# High_Speed_User_IO.net
KiCad netlist of a schematic drawn in Altium Designer
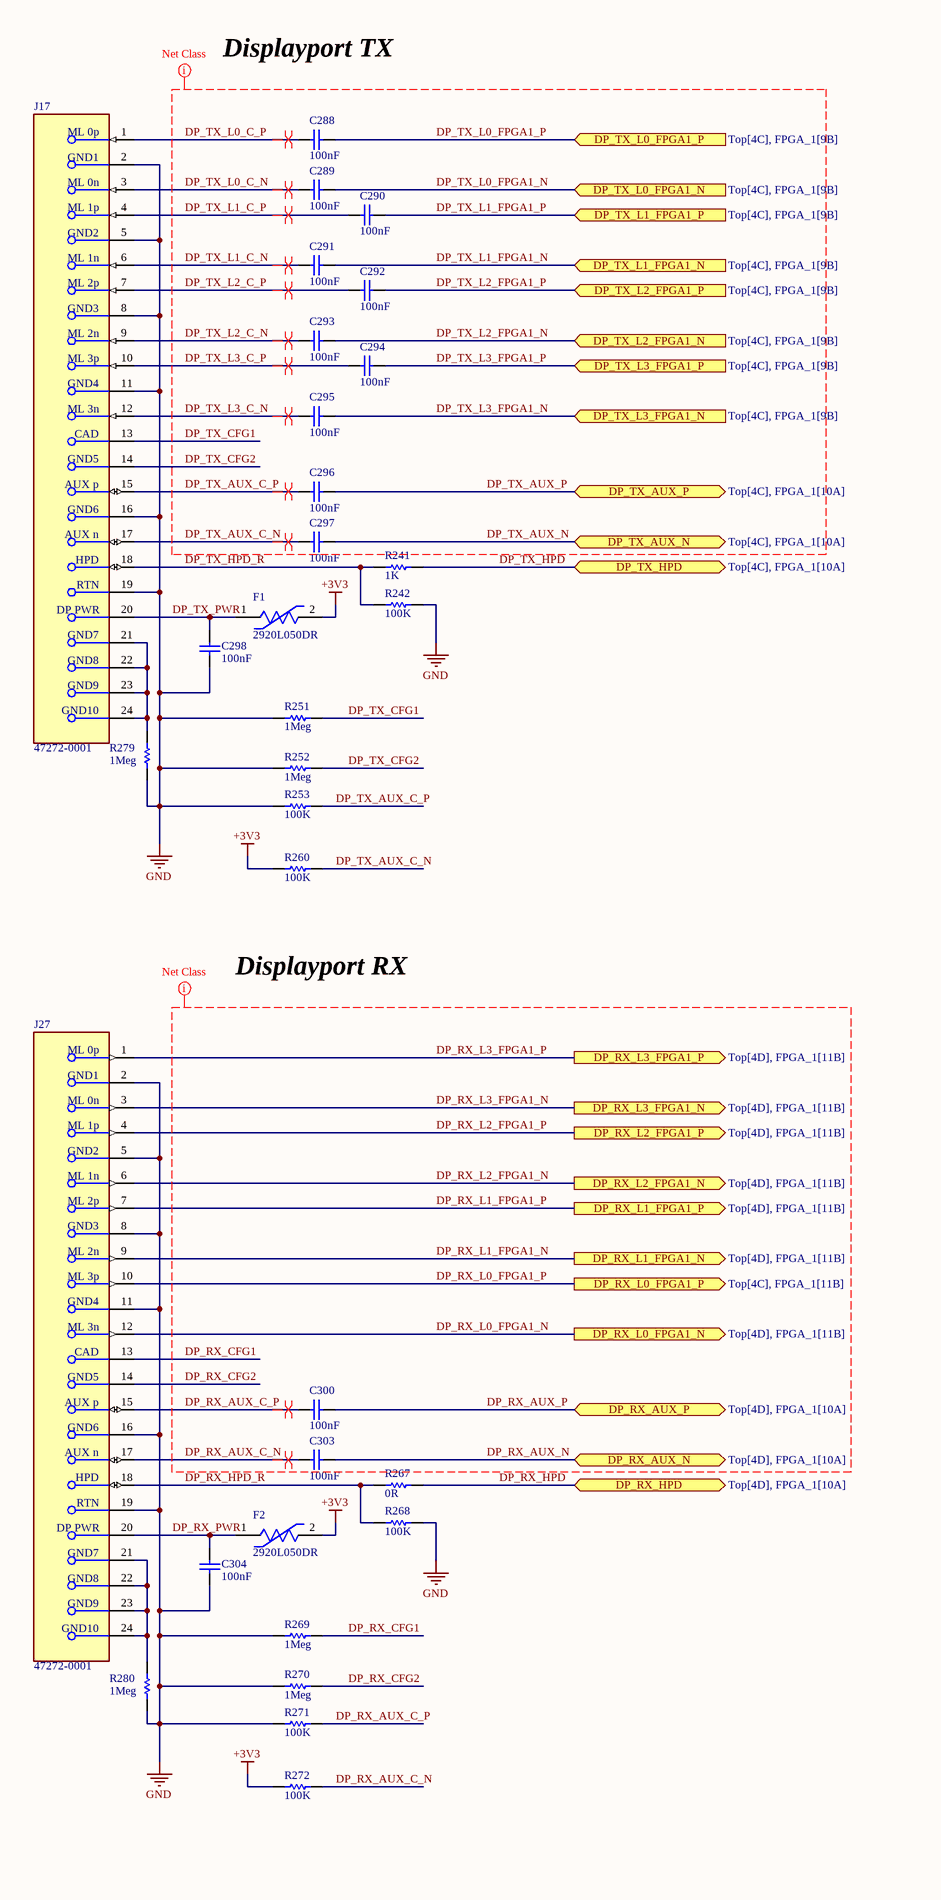
[diagram p0: High Speed User IO.SchDoc, left]
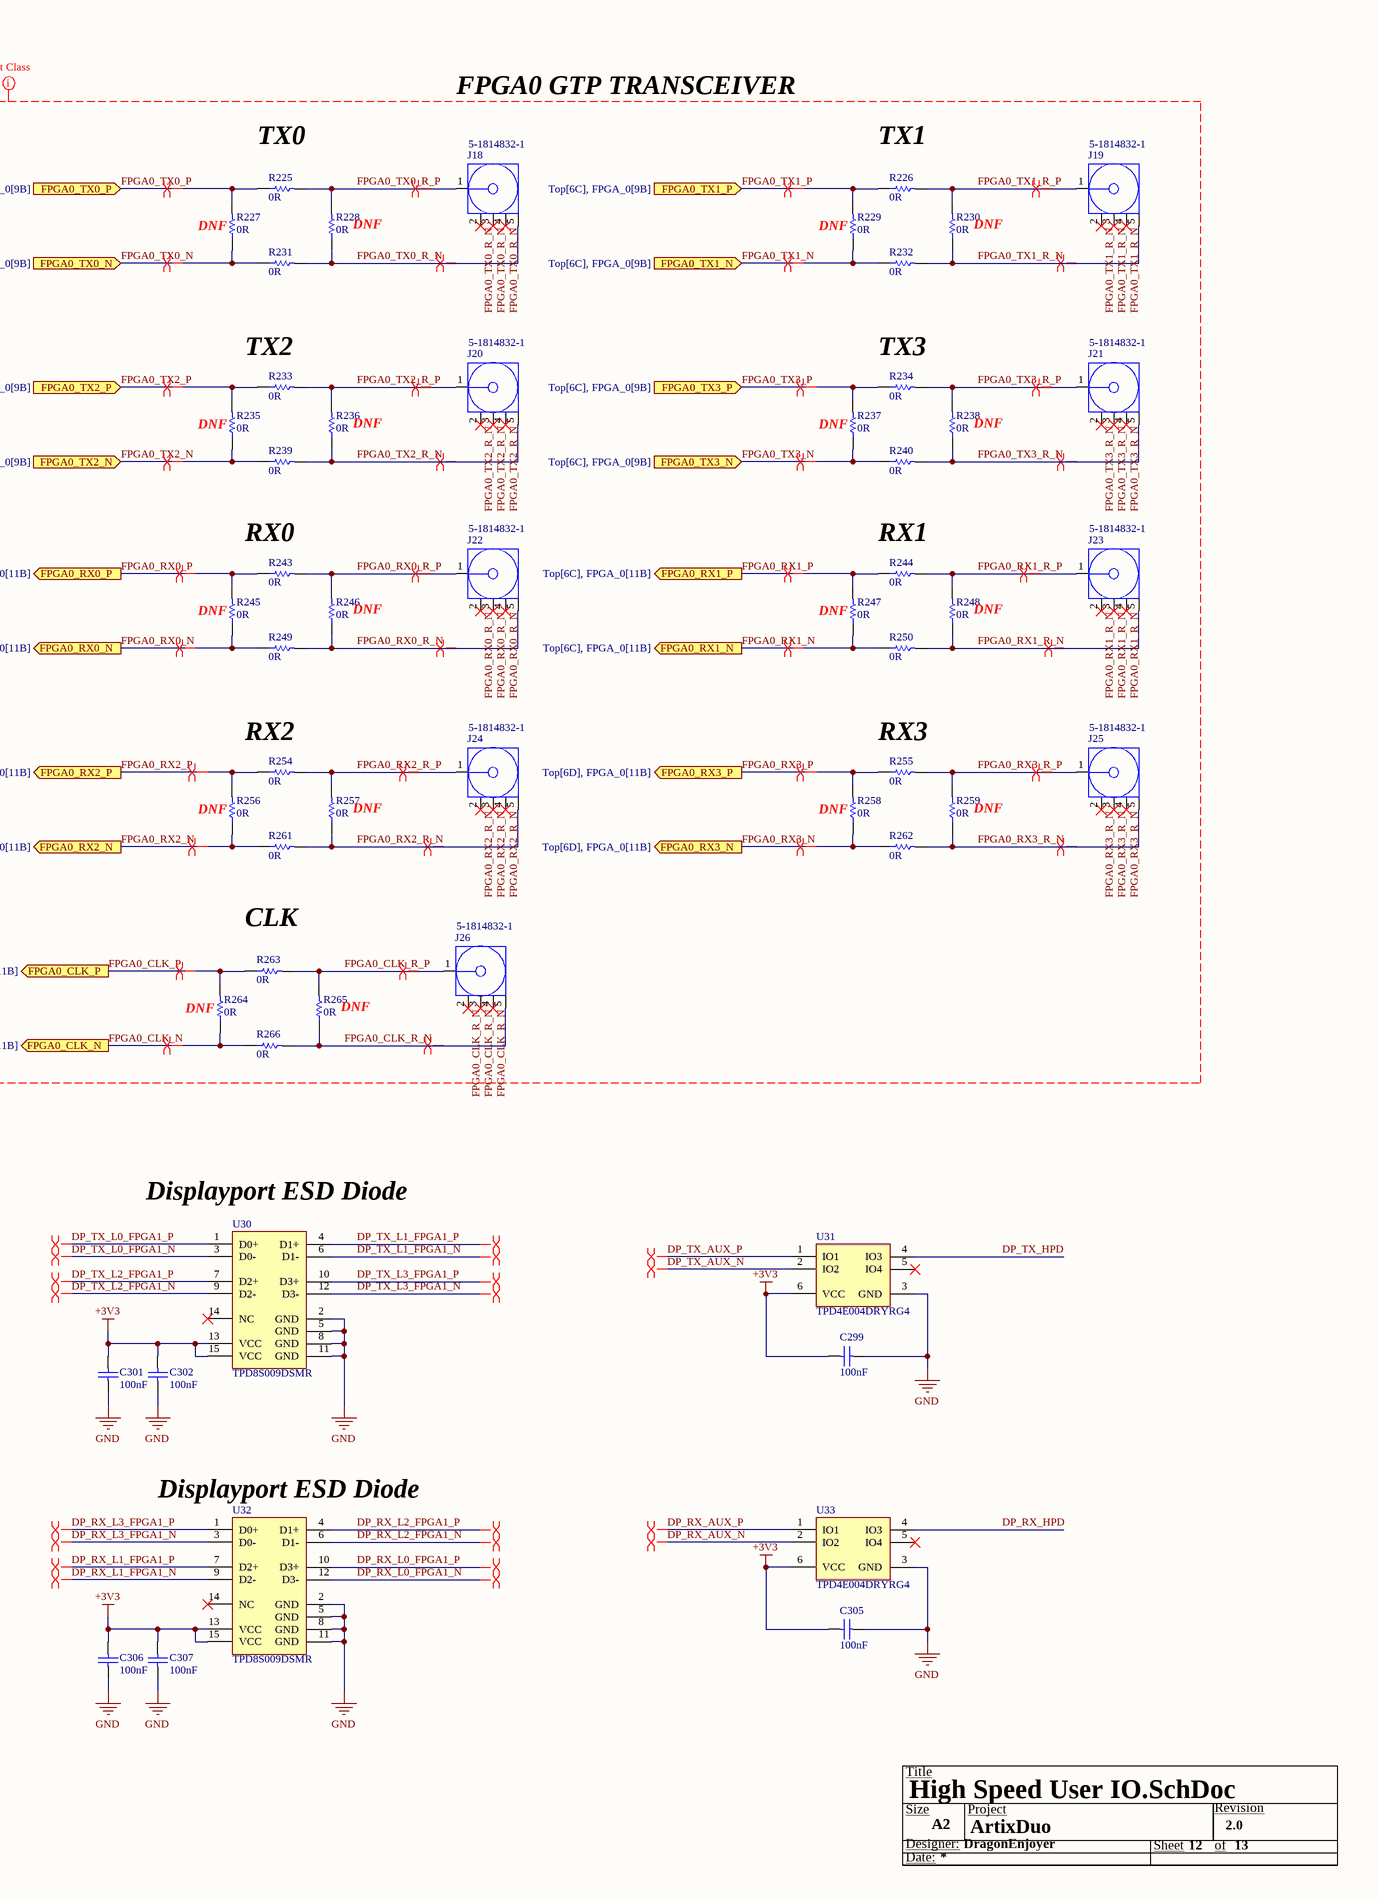
[diagram p1: High Speed User IO.SchDoc, right]

(export (version "E")
  (design (tool "Eeschema 10.0.6"))
  (components
    (comp (ref "C288")
      (value "100nF")
      (footprint "CAPC1005X05N")
      (description "Cap Ceramic 0.1uF 50V X7R 20% SMD 0402 125°C Paper T/R GRM155R71H104ME14J")
      (fields (field (name "VOLTAGE") "50V"))
      (libsource (lib "Main Workspace") (part "CAP"))
    )
    (comp (ref "C289")
      (value "100nF")
      (footprint "CAPC1005X05N")
      (description "Cap Ceramic 0.1uF 50V X7R 20% SMD 0402 125°C Paper T/R GRM155R71H104ME14J")
      (fields (field (name "VOLTAGE") "50V"))
      (libsource (lib "Main Workspace") (part "CAP"))
    )
    (comp (ref "C290")
      (value "100nF")
      (footprint "CAPC1005X05N")
      (description "Cap Ceramic 0.1uF 50V X7R 20% SMD 0402 125°C Paper T/R GRM155R71H104ME14J")
      (fields (field (name "VOLTAGE") "50V"))
      (libsource (lib "Main Workspace") (part "CAP"))
    )
    (comp (ref "C291")
      (value "100nF")
      (footprint "CAPC1005X05N")
      (description "Cap Ceramic 0.1uF 50V X7R 20% SMD 0402 125°C Paper T/R GRM155R71H104ME14J")
      (fields (field (name "VOLTAGE") "50V"))
      (libsource (lib "Main Workspace") (part "CAP"))
    )
    (comp (ref "C292")
      (value "100nF")
      (footprint "CAPC1005X05N")
      (description "Cap Ceramic 0.1uF 50V X7R 20% SMD 0402 125°C Paper T/R GRM155R71H104ME14J")
      (fields (field (name "VOLTAGE") "50V"))
      (libsource (lib "Main Workspace") (part "CAP"))
    )
    (comp (ref "C293")
      (value "100nF")
      (footprint "CAPC1005X05N")
      (description "Cap Ceramic 0.1uF 50V X7R 20% SMD 0402 125°C Paper T/R GRM155R71H104ME14J")
      (fields (field (name "VOLTAGE") "50V"))
      (libsource (lib "Main Workspace") (part "CAP"))
    )
    (comp (ref "C294")
      (value "100nF")
      (footprint "CAPC1005X05N")
      (description "Cap Ceramic 0.1uF 50V X7R 20% SMD 0402 125°C Paper T/R GRM155R71H104ME14J")
      (fields (field (name "VOLTAGE") "50V"))
      (libsource (lib "Main Workspace") (part "CAP"))
    )
    (comp (ref "C295")
      (value "100nF")
      (footprint "CAPC1005X05N")
      (description "Cap Ceramic 0.1uF 50V X7R 20% SMD 0402 125°C Paper T/R GRM155R71H104ME14J")
      (fields (field (name "VOLTAGE") "50V"))
      (libsource (lib "Main Workspace") (part "CAP"))
    )
    (comp (ref "C296")
      (value "100nF")
      (footprint "CAPC1005X05N")
      (description "Cap Ceramic 0.1uF 50V X7R 20% SMD 0402 125°C Paper T/R GRM155R71H104ME14J")
      (fields (field (name "VOLTAGE") "50V"))
      (libsource (lib "Main Workspace") (part "CAP"))
    )
    (comp (ref "C297")
      (value "100nF")
      (footprint "CAPC1005X05N")
      (description "Cap Ceramic 0.1uF 50V X7R 20% SMD 0402 125°C Paper T/R GRM155R71H104ME14J")
      (fields (field (name "VOLTAGE") "50V"))
      (libsource (lib "Main Workspace") (part "CAP"))
    )
    (comp (ref "C298")
      (value "100nF")
      (footprint "CAPC1005X05N")
      (description "Cap Ceramic 0.1uF 50V X7R 20% SMD 0402 125°C Paper T/R GRM155R71H104ME14J")
      (fields (field (name "VOLTAGE") "50V"))
      (libsource (lib "Main Workspace") (part "CAP"))
    )
    (comp (ref "C299")
      (value "100nF")
      (footprint "CAPC1005X05N")
      (description "Cap Ceramic 0.1uF 50V X7R 20% SMD 0402 125°C Paper T/R GRM155R71H104ME14J")
      (fields (field (name "VOLTAGE") "50V"))
      (libsource (lib "Main Workspace") (part "CAP"))
    )
    (comp (ref "C300")
      (value "100nF")
      (footprint "CAPC1005X05N")
      (description "Cap Ceramic 0.1uF 50V X7R 20% SMD 0402 125°C Paper T/R GRM155R71H104ME14J")
      (fields (field (name "VOLTAGE") "50V"))
      (libsource (lib "Main Workspace") (part "CAP"))
    )
    (comp (ref "C301")
      (value "100nF")
      (footprint "CAPC1005X05N")
      (description "Cap Ceramic 0.1uF 50V X7R 20% SMD 0402 125°C Paper T/R GRM155R71H104ME14J")
      (fields (field (name "VOLTAGE") "50V"))
      (libsource (lib "Main Workspace") (part "CAP"))
    )
    (comp (ref "C302")
      (value "100nF")
      (footprint "CAPC1005X05N")
      (description "Cap Ceramic 0.1uF 50V X7R 20% SMD 0402 125°C Paper T/R GRM155R71H104ME14J")
      (fields (field (name "VOLTAGE") "50V"))
      (libsource (lib "Main Workspace") (part "CAP"))
    )
    (comp (ref "C303")
      (value "100nF")
      (footprint "CAPC1005X05N")
      (description "Cap Ceramic 0.1uF 50V X7R 20% SMD 0402 125°C Paper T/R GRM155R71H104ME14J")
      (fields (field (name "VOLTAGE") "50V"))
      (libsource (lib "Main Workspace") (part "CAP"))
    )
    (comp (ref "C304")
      (value "100nF")
      (footprint "CAPC1005X05N")
      (description "Cap Ceramic 0.1uF 50V X7R 20% SMD 0402 125°C Paper T/R GRM155R71H104ME14J")
      (fields (field (name "VOLTAGE") "50V"))
      (libsource (lib "Main Workspace") (part "CAP"))
    )
    (comp (ref "C305")
      (value "100nF")
      (footprint "CAPC1005X05N")
      (description "Cap Ceramic 0.1uF 50V X7R 20% SMD 0402 125°C Paper T/R GRM155R71H104ME14J")
      (fields (field (name "VOLTAGE") "50V"))
      (libsource (lib "Main Workspace") (part "CAP"))
    )
    (comp (ref "C306")
      (value "100nF")
      (footprint "CAPC1005X05N")
      (description "Cap Ceramic 0.1uF 50V X7R 20% SMD 0402 125°C Paper T/R GRM155R71H104ME14J")
      (fields (field (name "VOLTAGE") "50V"))
      (libsource (lib "Main Workspace") (part "CAP"))
    )
    (comp (ref "C307")
      (value "100nF")
      (footprint "CAPC1005X05N")
      (description "Cap Ceramic 0.1uF 50V X7R 20% SMD 0402 125°C Paper T/R GRM155R71H104ME14J")
      (fields (field (name "VOLTAGE") "50V"))
      (libsource (lib "Main Workspace") (part "CAP"))
    )
    (comp (ref "F1")
      (value "2920L050DR")
      (footprint "FP-2920L050DR-MFG")
      (description "PTC RESET FUSE 60V 500MA 2920")
      (libsource (lib "Altium Content Vault") (part "1c6d77a0208143737455a0c7eb396be"))
    )
    (comp (ref "F2")
      (value "2920L050DR")
      (footprint "FP-2920L050DR-MFG")
      (description "PTC RESET FUSE 60V 500MA 2920")
      (libsource (lib "Altium Content Vault") (part "1c6d77a0208143737455a0c7eb396be"))
    )
    (comp (ref "J17")
      (value "47272-0001")
      (footprint "FP-47272-0001-MFG")
      (description "CONN RCPT DISPLAYPORT 20P SMD RA")
      (fields
        (field (name "MANUFACTURER") "Molex")
        (field (name "OCTOPART") "https://octopart.com/47272-0001-molex-5441289")
      )
      (libsource (lib "Altium Content Vault") (part "2afa8ceb06c8af4017661051ea5ebc1"))
    )
    (comp (ref "J18")
      (value "5-1814832-1")
      (footprint "TECO-5-1814832-1_V")
      (fields (field (name "MANUFACTURER") "TE Connectivity"))
      (libsource (lib "Altium Content Vault") (part "CN-S-4F-RF5"))
    )
    (comp (ref "J19")
      (value "5-1814832-1")
      (footprint "TECO-5-1814832-1_V")
      (fields (field (name "MANUFACTURER") "TE Connectivity"))
      (libsource (lib "Altium Content Vault") (part "CN-S-4F-RF5"))
    )
    (comp (ref "J20")
      (value "5-1814832-1")
      (footprint "TECO-5-1814832-1_V")
      (fields (field (name "MANUFACTURER") "TE Connectivity"))
      (libsource (lib "Altium Content Vault") (part "CN-S-4F-RF5"))
    )
    (comp (ref "J21")
      (value "5-1814832-1")
      (footprint "TECO-5-1814832-1_V")
      (fields (field (name "MANUFACTURER") "TE Connectivity"))
      (libsource (lib "Altium Content Vault") (part "CN-S-4F-RF5"))
    )
    (comp (ref "J22")
      (value "5-1814832-1")
      (footprint "TECO-5-1814832-1_V")
      (fields (field (name "MANUFACTURER") "TE Connectivity"))
      (libsource (lib "Altium Content Vault") (part "CN-S-4F-RF5"))
    )
    (comp (ref "J23")
      (value "5-1814832-1")
      (footprint "TECO-5-1814832-1_V")
      (fields (field (name "MANUFACTURER") "TE Connectivity"))
      (libsource (lib "Altium Content Vault") (part "CN-S-4F-RF5"))
    )
    (comp (ref "J24")
      (value "5-1814832-1")
      (footprint "TECO-5-1814832-1_V")
      (fields (field (name "MANUFACTURER") "TE Connectivity"))
      (libsource (lib "Altium Content Vault") (part "CN-S-4F-RF5"))
    )
    (comp (ref "J25")
      (value "5-1814832-1")
      (footprint "TECO-5-1814832-1_V")
      (fields (field (name "MANUFACTURER") "TE Connectivity"))
      (libsource (lib "Altium Content Vault") (part "CN-S-4F-RF5"))
    )
    (comp (ref "J26")
      (value "5-1814832-1")
      (footprint "TECO-5-1814832-1_V")
      (fields (field (name "MANUFACTURER") "TE Connectivity"))
      (libsource (lib "Altium Content Vault") (part "CN-S-4F-RF5"))
    )
    (comp (ref "J27")
      (value "47272-0001")
      (footprint "FP-47272-0001-MFG")
      (description "CONN RCPT DISPLAYPORT 20P SMD RA")
      (fields
        (field (name "MANUFACTURER") "Molex")
        (field (name "OCTOPART") "https://octopart.com/47272-0001-molex-5441289")
      )
      (libsource (lib "Altium Content Vault") (part "2afa8ceb06c8af4017661051ea5ebc1"))
    )
    (comp (ref "R225")
      (value "0R")
      (footprint "RESC1005X40X25NL05T10")
      (description "CRCW04020000Z0EDHP")
      (fields (field (name "MANUFACTURER") "Vishay Dale"))
      (libsource (lib "Altium Content Vault") (part "RES"))
    )
    (comp (ref "R226")
      (value "0R")
      (footprint "RESC1005X40X25NL05T10")
      (description "CRCW04020000Z0EDHP")
      (fields (field (name "MANUFACTURER") "Vishay Dale"))
      (libsource (lib "Altium Content Vault") (part "RES"))
    )
    (comp (ref "R227")
      (value "0R")
      (footprint "RESC1005X40X25NL05T10")
      (description "CRCW04020000Z0EDHP")
      (fields (field (name "MANUFACTURER") "Vishay Dale"))
      (libsource (lib "Altium Content Vault") (part "RES"))
    )
    (comp (ref "R228")
      (value "0R")
      (footprint "RESC1005X40X25NL05T10")
      (description "CRCW04020000Z0EDHP")
      (fields (field (name "MANUFACTURER") "Vishay Dale"))
      (libsource (lib "Altium Content Vault") (part "RES"))
    )
    (comp (ref "R229")
      (value "0R")
      (footprint "RESC1005X40X25NL05T10")
      (description "CRCW04020000Z0EDHP")
      (fields (field (name "MANUFACTURER") "Vishay Dale"))
      (libsource (lib "Altium Content Vault") (part "RES"))
    )
    (comp (ref "R230")
      (value "0R")
      (footprint "RESC1005X40X25NL05T10")
      (description "CRCW04020000Z0EDHP")
      (fields (field (name "MANUFACTURER") "Vishay Dale"))
      (libsource (lib "Altium Content Vault") (part "RES"))
    )
    (comp (ref "R231")
      (value "0R")
      (footprint "RESC1005X40X25NL05T10")
      (description "CRCW04020000Z0EDHP")
      (fields (field (name "MANUFACTURER") "Vishay Dale"))
      (libsource (lib "Altium Content Vault") (part "RES"))
    )
    (comp (ref "R232")
      (value "0R")
      (footprint "RESC1005X40X25NL05T10")
      (description "CRCW04020000Z0EDHP")
      (fields (field (name "MANUFACTURER") "Vishay Dale"))
      (libsource (lib "Altium Content Vault") (part "RES"))
    )
    (comp (ref "R233")
      (value "0R")
      (footprint "RESC1005X40X25NL05T10")
      (description "CRCW04020000Z0EDHP")
      (fields (field (name "MANUFACTURER") "Vishay Dale"))
      (libsource (lib "Altium Content Vault") (part "RES"))
    )
    (comp (ref "R234")
      (value "0R")
      (footprint "RESC1005X40X25NL05T10")
      (description "CRCW04020000Z0EDHP")
      (fields (field (name "MANUFACTURER") "Vishay Dale"))
      (libsource (lib "Altium Content Vault") (part "RES"))
    )
    (comp (ref "R235")
      (value "0R")
      (footprint "RESC1005X40X25NL05T10")
      (description "CRCW04020000Z0EDHP")
      (fields (field (name "MANUFACTURER") "Vishay Dale"))
      (libsource (lib "Altium Content Vault") (part "RES"))
    )
    (comp (ref "R236")
      (value "0R")
      (footprint "RESC1005X40X25NL05T10")
      (description "CRCW04020000Z0EDHP")
      (fields (field (name "MANUFACTURER") "Vishay Dale"))
      (libsource (lib "Altium Content Vault") (part "RES"))
    )
    (comp (ref "R237")
      (value "0R")
      (footprint "RESC1005X40X25NL05T10")
      (description "CRCW04020000Z0EDHP")
      (fields (field (name "MANUFACTURER") "Vishay Dale"))
      (libsource (lib "Altium Content Vault") (part "RES"))
    )
    (comp (ref "R238")
      (value "0R")
      (footprint "RESC1005X40X25NL05T10")
      (description "CRCW04020000Z0EDHP")
      (fields (field (name "MANUFACTURER") "Vishay Dale"))
      (libsource (lib "Altium Content Vault") (part "RES"))
    )
    (comp (ref "R239")
      (value "0R")
      (footprint "RESC1005X40X25NL05T10")
      (description "CRCW04020000Z0EDHP")
      (fields (field (name "MANUFACTURER") "Vishay Dale"))
      (libsource (lib "Altium Content Vault") (part "RES"))
    )
    (comp (ref "R240")
      (value "0R")
      (footprint "RESC1005X40X25NL05T10")
      (description "CRCW04020000Z0EDHP")
      (fields (field (name "MANUFACTURER") "Vishay Dale"))
      (libsource (lib "Altium Content Vault") (part "RES"))
    )
    (comp (ref "R241")
      (value "1K")
      (footprint "RESC1005X40X25NL05T10")
      (description "CRCW04021K00FKEDHP")
      (fields (field (name "MANUFACTURER") "Vishay Dale"))
      (libsource (lib "Altium Content Vault") (part "RES"))
    )
    (comp (ref "R242")
      (value "100K")
      (footprint "RESC1005X40X25NL05T05")
      (description "CRCW0402100KJNED")
      (fields (field (name "MANUFACTURER") "Vishay Dale"))
      (libsource (lib "Altium Content Vault") (part "RES"))
    )
    (comp (ref "R243")
      (value "0R")
      (footprint "RESC1005X40X25NL05T10")
      (description "CRCW04020000Z0EDHP")
      (fields (field (name "MANUFACTURER") "Vishay Dale"))
      (libsource (lib "Altium Content Vault") (part "RES"))
    )
    (comp (ref "R244")
      (value "0R")
      (footprint "RESC1005X40X25NL05T10")
      (description "CRCW04020000Z0EDHP")
      (fields (field (name "MANUFACTURER") "Vishay Dale"))
      (libsource (lib "Altium Content Vault") (part "RES"))
    )
    (comp (ref "R245")
      (value "0R")
      (footprint "RESC1005X40X25NL05T10")
      (description "CRCW04020000Z0EDHP")
      (fields (field (name "MANUFACTURER") "Vishay Dale"))
      (libsource (lib "Altium Content Vault") (part "RES"))
    )
    (comp (ref "R246")
      (value "0R")
      (footprint "RESC1005X40X25NL05T10")
      (description "CRCW04020000Z0EDHP")
      (fields (field (name "MANUFACTURER") "Vishay Dale"))
      (libsource (lib "Altium Content Vault") (part "RES"))
    )
    (comp (ref "R247")
      (value "0R")
      (footprint "RESC1005X40X25NL05T10")
      (description "CRCW04020000Z0EDHP")
      (fields (field (name "MANUFACTURER") "Vishay Dale"))
      (libsource (lib "Altium Content Vault") (part "RES"))
    )
    (comp (ref "R248")
      (value "0R")
      (footprint "RESC1005X40X25NL05T10")
      (description "CRCW04020000Z0EDHP")
      (fields (field (name "MANUFACTURER") "Vishay Dale"))
      (libsource (lib "Altium Content Vault") (part "RES"))
    )
    (comp (ref "R249")
      (value "0R")
      (footprint "RESC1005X40X25NL05T10")
      (description "CRCW04020000Z0EDHP")
      (fields (field (name "MANUFACTURER") "Vishay Dale"))
      (libsource (lib "Altium Content Vault") (part "RES"))
    )
    (comp (ref "R250")
      (value "0R")
      (footprint "RESC1005X40X25NL05T10")
      (description "CRCW04020000Z0EDHP")
      (fields (field (name "MANUFACTURER") "Vishay Dale"))
      (libsource (lib "Altium Content Vault") (part "RES"))
    )
    (comp (ref "R251")
      (value "1Meg")
      (footprint "RESC1005X40X25NL05T05")
      (description "ERJ-2GEJ105X")
      (fields (field (name "MANUFACTURER") "Panasonic"))
      (libsource (lib "Altium Content Vault") (part "RES"))
    )
    (comp (ref "R252")
      (value "1Meg")
      (footprint "RESC1005X40X25NL05T05")
      (description "ERJ-2GEJ105X")
      (fields (field (name "MANUFACTURER") "Panasonic"))
      (libsource (lib "Altium Content Vault") (part "RES"))
    )
    (comp (ref "R253")
      (value "100K")
      (footprint "RESC1005X40X25NL05T05")
      (description "CRCW0402100KJNED")
      (fields (field (name "MANUFACTURER") "Vishay Dale"))
      (libsource (lib "Altium Content Vault") (part "RES"))
    )
    (comp (ref "R254")
      (value "0R")
      (footprint "RESC1005X40X25NL05T10")
      (description "CRCW04020000Z0EDHP")
      (fields (field (name "MANUFACTURER") "Vishay Dale"))
      (libsource (lib "Altium Content Vault") (part "RES"))
    )
    (comp (ref "R255")
      (value "0R")
      (footprint "RESC1005X40X25NL05T10")
      (description "CRCW04020000Z0EDHP")
      (fields (field (name "MANUFACTURER") "Vishay Dale"))
      (libsource (lib "Altium Content Vault") (part "RES"))
    )
    (comp (ref "R256")
      (value "0R")
      (footprint "RESC1005X40X25NL05T10")
      (description "CRCW04020000Z0EDHP")
      (fields (field (name "MANUFACTURER") "Vishay Dale"))
      (libsource (lib "Altium Content Vault") (part "RES"))
    )
    (comp (ref "R257")
      (value "0R")
      (footprint "RESC1005X40X25NL05T10")
      (description "CRCW04020000Z0EDHP")
      (fields (field (name "MANUFACTURER") "Vishay Dale"))
      (libsource (lib "Altium Content Vault") (part "RES"))
    )
    (comp (ref "R258")
      (value "0R")
      (footprint "RESC1005X40X25NL05T10")
      (description "CRCW04020000Z0EDHP")
      (fields (field (name "MANUFACTURER") "Vishay Dale"))
      (libsource (lib "Altium Content Vault") (part "RES"))
    )
    (comp (ref "R259")
      (value "0R")
      (footprint "RESC1005X40X25NL05T10")
      (description "CRCW04020000Z0EDHP")
      (fields (field (name "MANUFACTURER") "Vishay Dale"))
      (libsource (lib "Altium Content Vault") (part "RES"))
    )
    (comp (ref "R260")
      (value "100K")
      (footprint "RESC1005X40X25NL05T05")
      (description "CRCW0402100KJNED")
      (fields (field (name "MANUFACTURER") "Vishay Dale"))
      (libsource (lib "Altium Content Vault") (part "RES"))
    )
    (comp (ref "R261")
      (value "0R")
      (footprint "RESC1005X40X25NL05T10")
      (description "CRCW04020000Z0EDHP")
      (fields (field (name "MANUFACTURER") "Vishay Dale"))
      (libsource (lib "Altium Content Vault") (part "RES"))
    )
    (comp (ref "R262")
      (value "0R")
      (footprint "RESC1005X40X25NL05T10")
      (description "CRCW04020000Z0EDHP")
      (fields (field (name "MANUFACTURER") "Vishay Dale"))
      (libsource (lib "Altium Content Vault") (part "RES"))
    )
    (comp (ref "R263")
      (value "0R")
      (footprint "RESC1005X40X25NL05T10")
      (description "CRCW04020000Z0EDHP")
      (fields (field (name "MANUFACTURER") "Vishay Dale"))
      (libsource (lib "Altium Content Vault") (part "RES"))
    )
    (comp (ref "R264")
      (value "0R")
      (footprint "RESC1005X40X25NL05T10")
      (description "CRCW04020000Z0EDHP")
      (fields (field (name "MANUFACTURER") "Vishay Dale"))
      (libsource (lib "Altium Content Vault") (part "RES"))
    )
    (comp (ref "R265")
      (value "0R")
      (footprint "RESC1005X40X25NL05T10")
      (description "CRCW04020000Z0EDHP")
      (fields (field (name "MANUFACTURER") "Vishay Dale"))
      (libsource (lib "Altium Content Vault") (part "RES"))
    )
    (comp (ref "R266")
      (value "0R")
      (footprint "RESC1005X40X25NL05T10")
      (description "CRCW04020000Z0EDHP")
      (fields (field (name "MANUFACTURER") "Vishay Dale"))
      (libsource (lib "Altium Content Vault") (part "RES"))
    )
    (comp (ref "R267")
      (value "0R")
      (footprint "RESC1005X40X25NL05T10")
      (description "CRCW04020000Z0EDHP")
      (fields (field (name "MANUFACTURER") "Vishay Dale"))
      (libsource (lib "Altium Content Vault") (part "RES"))
    )
    (comp (ref "R268")
      (value "100K")
      (footprint "RESC1005X40X25NL05T05")
      (description "CRCW0402100KJNED")
      (fields (field (name "MANUFACTURER") "Vishay Dale"))
      (libsource (lib "Altium Content Vault") (part "RES"))
    )
    (comp (ref "R269")
      (value "1Meg")
      (footprint "RESC1005X40X25NL05T05")
      (description "ERJ-2GEJ105X")
      (fields (field (name "MANUFACTURER") "Panasonic"))
      (libsource (lib "Altium Content Vault") (part "RES"))
    )
    (comp (ref "R270")
      (value "1Meg")
      (footprint "RESC1005X40X25NL05T05")
      (description "ERJ-2GEJ105X")
      (fields (field (name "MANUFACTURER") "Panasonic"))
      (libsource (lib "Altium Content Vault") (part "RES"))
    )
    (comp (ref "R271")
      (value "100K")
      (footprint "RESC1005X40X25NL05T05")
      (description "CRCW0402100KJNED")
      (fields (field (name "MANUFACTURER") "Vishay Dale"))
      (libsource (lib "Altium Content Vault") (part "RES"))
    )
    (comp (ref "R272")
      (value "100K")
      (footprint "RESC1005X40X25NL05T05")
      (description "CRCW0402100KJNED")
      (fields (field (name "MANUFACTURER") "Vishay Dale"))
      (libsource (lib "Altium Content Vault") (part "RES"))
    )
    (comp (ref "R279")
      (value "1Meg")
      (footprint "RESC1005X40X25NL05T05")
      (description "ERJ-2GEJ105X")
      (fields (field (name "MANUFACTURER") "Panasonic"))
      (libsource (lib "Altium Content Vault") (part "RES"))
    )
    (comp (ref "R280")
      (value "1Meg")
      (footprint "RESC1005X40X25NL05T05")
      (description "ERJ-2GEJ105X")
      (fields (field (name "MANUFACTURER") "Panasonic"))
      (libsource (lib "Altium Content Vault") (part "RES"))
    )
    (comp (ref "U30")
      (value "TPD8S009DSMR")
      (footprint "DSM0015A_V")
      (description "ESD Solution for HDMI / DisplayPort, 8 Channels, -40 to +85 degC, 15-pin SON (DSM)")
      (fields (field (name "MANUFACTURER") "Texas Instruments"))
      (libsource (lib "Altium Content Vault") (part "TI-TPD8S009-SON_DSM-15"))
    )
    (comp (ref "U31")
      (value "TPD4E004DRYRG4")
      (footprint "DRY0006A")
      (fields (field (name "MANUFACTURER") "Texas Instruments"))
      (libsource (lib "Altium Content Vault") (part "TI-TPD4E004-SON_DRY-6"))
    )
    (comp (ref "U32")
      (value "TPD8S009DSMR")
      (footprint "DSM0015A_V")
      (description "ESD Solution for HDMI / DisplayPort, 8 Channels, -40 to +85 degC, 15-pin SON (DSM)")
      (fields (field (name "MANUFACTURER") "Texas Instruments"))
      (libsource (lib "Altium Content Vault") (part "TI-TPD8S009-SON_DSM-15"))
    )
    (comp (ref "U33")
      (value "TPD4E004DRYRG4")
      (footprint "DRY0006A")
      (fields (field (name "MANUFACTURER") "Texas Instruments"))
      (libsource (lib "Altium Content Vault") (part "TI-TPD4E004-SON_DRY-6"))
    )
  )
  (nets
    (net (code "1") (name "+3V3") (class "Default")
      (node (ref "C299") (pin "1") (pinfunction "1_1") (pintype "passive"))
      (node (ref "C301") (pin "1") (pinfunction "1_1") (pintype "passive"))
      (node (ref "C302") (pin "1") (pinfunction "1_1") (pintype "passive"))
      (node (ref "C305") (pin "1") (pinfunction "1_1") (pintype "passive"))
      (node (ref "C306") (pin "1") (pinfunction "1_1") (pintype "passive"))
      (node (ref "C307") (pin "1") (pinfunction "1_1") (pintype "passive"))
      (node (ref "F1") (pin "2") (pinfunction "2_2") (pintype "passive"))
      (node (ref "F2") (pin "2") (pinfunction "2_2") (pintype "passive"))
      (node (ref "R260") (pin "1") (pinfunction "1_1") (pintype "passive"))
      (node (ref "R272") (pin "1") (pinfunction "1_1") (pintype "passive"))
      (node (ref "U30") (pin "13") (pinfunction "VCC_13") (pintype "power_in"))
      (node (ref "U30") (pin "15") (pinfunction "VCC_15") (pintype "power_in"))
      (node (ref "U31") (pin "6") (pinfunction "VCC_6") (pintype "power_in"))
      (node (ref "U32") (pin "13") (pinfunction "VCC_13") (pintype "power_in"))
      (node (ref "U32") (pin "15") (pinfunction "VCC_15") (pintype "power_in"))
      (node (ref "U33") (pin "6") (pinfunction "VCC_6") (pintype "power_in"))
    )
    (net (code "2") (name "/DP_RX_AUX_C_N") (class "Default")
      (node (ref "C303") (pin "2") (pinfunction "2_2") (pintype "passive"))
      (node (ref "J27") (pin "17") (pinfunction "AUX_n_17") (pintype "bidirectional"))
      (node (ref "R272") (pin "2") (pinfunction "2_2") (pintype "passive"))
    )
    (net (code "3") (name "/DP_RX_AUX_C_P") (class "Default")
      (node (ref "C300") (pin "2") (pinfunction "2_2") (pintype "passive"))
      (node (ref "J27") (pin "15") (pinfunction "AUX_p_15") (pintype "bidirectional"))
      (node (ref "R271") (pin "2") (pinfunction "2_2") (pintype "passive"))
    )
    (net (code "4") (name "/DP_RX_AUX_N") (class "Default")
      (node (ref "C303") (pin "1") (pinfunction "1_1") (pintype "passive"))
      (node (ref "U33") (pin "2") (pinfunction "IO2_2") (pintype "passive"))
    )
    (net (code "5") (name "/DP_RX_AUX_P") (class "Default")
      (node (ref "C300") (pin "1") (pinfunction "1_1") (pintype "passive"))
      (node (ref "U33") (pin "1") (pinfunction "IO1_1") (pintype "passive"))
    )
    (net (code "6") (name "/DP_RX_CFG1") (class "Default")
      (node (ref "J27") (pin "13") (pinfunction "CAD_13") (pintype "passive"))
      (node (ref "R269") (pin "2") (pinfunction "2_2") (pintype "passive"))
    )
    (net (code "7") (name "/DP_RX_CFG2") (class "Default")
      (node (ref "J27") (pin "14") (pinfunction "GND5_14") (pintype "power_in"))
      (node (ref "R270") (pin "2") (pinfunction "2_2") (pintype "passive"))
    )
    (net (code "8") (name "/DP_RX_HPD") (class "Default")
      (node (ref "R267") (pin "2") (pinfunction "2_2") (pintype "passive"))
      (node (ref "U33") (pin "4") (pinfunction "IO3_4") (pintype "passive"))
    )
    (net (code "9") (name "/DP_RX_HPD_R") (class "Default")
      (node (ref "J27") (pin "18") (pinfunction "HPD_18") (pintype "bidirectional"))
      (node (ref "R267") (pin "1") (pinfunction "1_1") (pintype "passive"))
      (node (ref "R268") (pin "1") (pinfunction "1_1") (pintype "passive"))
    )
    (net (code "10") (name "/DP_RX_L0_FPGA1_N") (class "Default")
      (node (ref "J27") (pin "12") (pinfunction "ML_3n_12") (pintype "input"))
      (node (ref "U32") (pin "12") (pinfunction "D3-_12") (pintype "passive"))
    )
    (net (code "11") (name "/DP_RX_L0_FPGA1_P") (class "Default")
      (node (ref "J27") (pin "10") (pinfunction "ML_3p_10") (pintype "input"))
      (node (ref "U32") (pin "10") (pinfunction "D3+_10") (pintype "passive"))
    )
    (net (code "12") (name "/DP_RX_L1_FPGA1_N") (class "Default")
      (node (ref "J27") (pin "9") (pinfunction "ML_2n_9") (pintype "input"))
      (node (ref "U32") (pin "9") (pinfunction "D2-_9") (pintype "passive"))
    )
    (net (code "13") (name "/DP_RX_L1_FPGA1_P") (class "Default")
      (node (ref "J27") (pin "7") (pinfunction "ML_2p_7") (pintype "input"))
      (node (ref "U32") (pin "7") (pinfunction "D2+_7") (pintype "passive"))
    )
    (net (code "14") (name "/DP_RX_L2_FPGA1_N") (class "Default")
      (node (ref "J27") (pin "6") (pinfunction "ML_1n_6") (pintype "input"))
      (node (ref "U32") (pin "6") (pinfunction "D1-_6") (pintype "passive"))
    )
    (net (code "15") (name "/DP_RX_L2_FPGA1_P") (class "Default")
      (node (ref "J27") (pin "4") (pinfunction "ML_1p_4") (pintype "input"))
      (node (ref "U32") (pin "4") (pinfunction "D1+_4") (pintype "passive"))
    )
    (net (code "16") (name "/DP_RX_L3_FPGA1_N") (class "Default")
      (node (ref "J27") (pin "3") (pinfunction "ML_0n_3") (pintype "input"))
      (node (ref "U32") (pin "3") (pinfunction "D0-_3") (pintype "passive"))
    )
    (net (code "17") (name "/DP_RX_L3_FPGA1_P") (class "Default")
      (node (ref "J27") (pin "1") (pinfunction "ML_0p_1") (pintype "input"))
      (node (ref "U32") (pin "1") (pinfunction "D0+_1") (pintype "passive"))
    )
    (net (code "18") (name "/DP_RX_PWR") (class "Default")
      (node (ref "C304") (pin "1") (pinfunction "1_1") (pintype "passive"))
      (node (ref "F2") (pin "1") (pinfunction "1_1") (pintype "passive"))
      (node (ref "J27") (pin "20") (pinfunction "DP_PWR_20") (pintype "passive"))
    )
    (net (code "19") (name "/DP_TX_AUX_C_N") (class "Default")
      (node (ref "C297") (pin "2") (pinfunction "2_2") (pintype "passive"))
      (node (ref "J17") (pin "17") (pinfunction "AUX_n_17") (pintype "bidirectional"))
      (node (ref "R260") (pin "2") (pinfunction "2_2") (pintype "passive"))
    )
    (net (code "20") (name "/DP_TX_AUX_C_P") (class "Default")
      (node (ref "C296") (pin "2") (pinfunction "2_2") (pintype "passive"))
      (node (ref "J17") (pin "15") (pinfunction "AUX_p_15") (pintype "bidirectional"))
      (node (ref "R253") (pin "2") (pinfunction "2_2") (pintype "passive"))
    )
    (net (code "21") (name "/DP_TX_AUX_N") (class "Default")
      (node (ref "C297") (pin "1") (pinfunction "1_1") (pintype "passive"))
      (node (ref "U31") (pin "2") (pinfunction "IO2_2") (pintype "passive"))
    )
    (net (code "22") (name "/DP_TX_AUX_P") (class "Default")
      (node (ref "C296") (pin "1") (pinfunction "1_1") (pintype "passive"))
      (node (ref "U31") (pin "1") (pinfunction "IO1_1") (pintype "passive"))
    )
    (net (code "23") (name "/DP_TX_CFG1") (class "Default")
      (node (ref "J17") (pin "13") (pinfunction "CAD_13") (pintype "passive"))
      (node (ref "R251") (pin "2") (pinfunction "2_2") (pintype "passive"))
    )
    (net (code "24") (name "/DP_TX_CFG2") (class "Default")
      (node (ref "J17") (pin "14") (pinfunction "GND5_14") (pintype "power_in"))
      (node (ref "R252") (pin "2") (pinfunction "2_2") (pintype "passive"))
    )
    (net (code "25") (name "/DP_TX_HPD") (class "Default")
      (node (ref "R241") (pin "2") (pinfunction "2_2") (pintype "passive"))
      (node (ref "U31") (pin "4") (pinfunction "IO3_4") (pintype "passive"))
    )
    (net (code "26") (name "/DP_TX_HPD_R") (class "Default")
      (node (ref "J17") (pin "18") (pinfunction "HPD_18") (pintype "bidirectional"))
      (node (ref "R241") (pin "1") (pinfunction "1_1") (pintype "passive"))
      (node (ref "R242") (pin "1") (pinfunction "1_1") (pintype "passive"))
    )
    (net (code "27") (name "/DP_TX_L0_C_N") (class "Default")
      (node (ref "C289") (pin "2") (pinfunction "2_2") (pintype "passive"))
      (node (ref "J17") (pin "3") (pinfunction "ML_0n_3") (pintype "input"))
    )
    (net (code "28") (name "/DP_TX_L0_C_P") (class "Default")
      (node (ref "C288") (pin "2") (pinfunction "2_2") (pintype "passive"))
      (node (ref "J17") (pin "1") (pinfunction "ML_0p_1") (pintype "input"))
    )
    (net (code "29") (name "/DP_TX_L0_FPGA1_N") (class "Default")
      (node (ref "C289") (pin "1") (pinfunction "1_1") (pintype "passive"))
      (node (ref "U30") (pin "3") (pinfunction "D0-_3") (pintype "passive"))
    )
    (net (code "30") (name "/DP_TX_L0_FPGA1_P") (class "Default")
      (node (ref "C288") (pin "1") (pinfunction "1_1") (pintype "passive"))
      (node (ref "U30") (pin "1") (pinfunction "D0+_1") (pintype "passive"))
    )
    (net (code "31") (name "/DP_TX_L1_C_N") (class "Default")
      (node (ref "C291") (pin "2") (pinfunction "2_2") (pintype "passive"))
      (node (ref "J17") (pin "6") (pinfunction "ML_1n_6") (pintype "input"))
    )
    (net (code "32") (name "/DP_TX_L1_C_P") (class "Default")
      (node (ref "C290") (pin "2") (pinfunction "2_2") (pintype "passive"))
      (node (ref "J17") (pin "4") (pinfunction "ML_1p_4") (pintype "input"))
    )
    (net (code "33") (name "/DP_TX_L1_FPGA1_N") (class "Default")
      (node (ref "C291") (pin "1") (pinfunction "1_1") (pintype "passive"))
      (node (ref "U30") (pin "6") (pinfunction "D1-_6") (pintype "passive"))
    )
    (net (code "34") (name "/DP_TX_L1_FPGA1_P") (class "Default")
      (node (ref "C290") (pin "1") (pinfunction "1_1") (pintype "passive"))
      (node (ref "U30") (pin "4") (pinfunction "D1+_4") (pintype "passive"))
    )
    (net (code "35") (name "/DP_TX_L2_C_N") (class "Default")
      (node (ref "C293") (pin "2") (pinfunction "2_2") (pintype "passive"))
      (node (ref "J17") (pin "9") (pinfunction "ML_2n_9") (pintype "input"))
    )
    (net (code "36") (name "/DP_TX_L2_C_P") (class "Default")
      (node (ref "C292") (pin "2") (pinfunction "2_2") (pintype "passive"))
      (node (ref "J17") (pin "7") (pinfunction "ML_2p_7") (pintype "input"))
    )
    (net (code "37") (name "/DP_TX_L2_FPGA1_N") (class "Default")
      (node (ref "C293") (pin "1") (pinfunction "1_1") (pintype "passive"))
      (node (ref "U30") (pin "9") (pinfunction "D2-_9") (pintype "passive"))
    )
    (net (code "38") (name "/DP_TX_L2_FPGA1_P") (class "Default")
      (node (ref "C292") (pin "1") (pinfunction "1_1") (pintype "passive"))
      (node (ref "U30") (pin "7") (pinfunction "D2+_7") (pintype "passive"))
    )
    (net (code "39") (name "/DP_TX_L3_C_N") (class "Default")
      (node (ref "C295") (pin "2") (pinfunction "2_2") (pintype "passive"))
      (node (ref "J17") (pin "12") (pinfunction "ML_3n_12") (pintype "input"))
    )
    (net (code "40") (name "/DP_TX_L3_C_P") (class "Default")
      (node (ref "C294") (pin "2") (pinfunction "2_2") (pintype "passive"))
      (node (ref "J17") (pin "10") (pinfunction "ML_3p_10") (pintype "input"))
    )
    (net (code "41") (name "/DP_TX_L3_FPGA1_N") (class "Default")
      (node (ref "C295") (pin "1") (pinfunction "1_1") (pintype "passive"))
      (node (ref "U30") (pin "12") (pinfunction "D3-_12") (pintype "passive"))
    )
    (net (code "42") (name "/DP_TX_L3_FPGA1_P") (class "Default")
      (node (ref "C294") (pin "1") (pinfunction "1_1") (pintype "passive"))
      (node (ref "U30") (pin "10") (pinfunction "D3+_10") (pintype "passive"))
    )
    (net (code "43") (name "/DP_TX_PWR") (class "Default")
      (node (ref "C298") (pin "1") (pinfunction "1_1") (pintype "passive"))
      (node (ref "F1") (pin "1") (pinfunction "1_1") (pintype "passive"))
      (node (ref "J17") (pin "20") (pinfunction "DP_PWR_20") (pintype "passive"))
    )
    (net (code "44") (name "/FPGA0_CLK_N") (class "Default")
      (node (ref "R264") (pin "1") (pinfunction "1_1") (pintype "passive"))
      (node (ref "R266") (pin "1") (pinfunction "1_1") (pintype "passive"))
    )
    (net (code "45") (name "/FPGA0_CLK_P") (class "Default")
      (node (ref "R263") (pin "1") (pinfunction "1_1") (pintype "passive"))
      (node (ref "R264") (pin "2") (pinfunction "2_2") (pintype "passive"))
    )
    (net (code "46") (name "/FPGA0_CLK_R_N") (class "Default")
      (node (ref "J26") (pin "2") (pinfunction "2_2") (pintype "passive"))
      (node (ref "J26") (pin "3") (pinfunction "3_3") (pintype "passive"))
      (node (ref "J26") (pin "4") (pinfunction "4_4") (pintype "passive"))
      (node (ref "J26") (pin "5") (pinfunction "5_5") (pintype "passive"))
      (node (ref "R265") (pin "1") (pinfunction "1_1") (pintype "passive"))
      (node (ref "R266") (pin "2") (pinfunction "2_2") (pintype "passive"))
    )
    (net (code "47") (name "/FPGA0_CLK_R_P") (class "Default")
      (node (ref "J26") (pin "1") (pinfunction "1_1") (pintype "passive"))
      (node (ref "R263") (pin "2") (pinfunction "2_2") (pintype "passive"))
      (node (ref "R265") (pin "2") (pinfunction "2_2") (pintype "passive"))
    )
    (net (code "48") (name "/FPGA0_RX0_N") (class "Default")
      (node (ref "R245") (pin "1") (pinfunction "1_1") (pintype "passive"))
      (node (ref "R249") (pin "1") (pinfunction "1_1") (pintype "passive"))
    )
    (net (code "49") (name "/FPGA0_RX0_P") (class "Default")
      (node (ref "R243") (pin "1") (pinfunction "1_1") (pintype "passive"))
      (node (ref "R245") (pin "2") (pinfunction "2_2") (pintype "passive"))
    )
    (net (code "50") (name "/FPGA0_RX0_R_N") (class "Default")
      (node (ref "J22") (pin "2") (pinfunction "2_2") (pintype "passive"))
      (node (ref "J22") (pin "3") (pinfunction "3_3") (pintype "passive"))
      (node (ref "J22") (pin "4") (pinfunction "4_4") (pintype "passive"))
      (node (ref "J22") (pin "5") (pinfunction "5_5") (pintype "passive"))
      (node (ref "R246") (pin "1") (pinfunction "1_1") (pintype "passive"))
      (node (ref "R249") (pin "2") (pinfunction "2_2") (pintype "passive"))
    )
    (net (code "51") (name "/FPGA0_RX0_R_P") (class "Default")
      (node (ref "J22") (pin "1") (pinfunction "1_1") (pintype "passive"))
      (node (ref "R243") (pin "2") (pinfunction "2_2") (pintype "passive"))
      (node (ref "R246") (pin "2") (pinfunction "2_2") (pintype "passive"))
    )
    (net (code "52") (name "/FPGA0_RX1_N") (class "Default")
      (node (ref "R247") (pin "1") (pinfunction "1_1") (pintype "passive"))
      (node (ref "R250") (pin "1") (pinfunction "1_1") (pintype "passive"))
    )
    (net (code "53") (name "/FPGA0_RX1_P") (class "Default")
      (node (ref "R244") (pin "1") (pinfunction "1_1") (pintype "passive"))
      (node (ref "R247") (pin "2") (pinfunction "2_2") (pintype "passive"))
    )
    (net (code "54") (name "/FPGA0_RX1_R_N") (class "Default")
      (node (ref "J23") (pin "2") (pinfunction "2_2") (pintype "passive"))
      (node (ref "J23") (pin "3") (pinfunction "3_3") (pintype "passive"))
      (node (ref "J23") (pin "4") (pinfunction "4_4") (pintype "passive"))
      (node (ref "J23") (pin "5") (pinfunction "5_5") (pintype "passive"))
      (node (ref "R248") (pin "1") (pinfunction "1_1") (pintype "passive"))
      (node (ref "R250") (pin "2") (pinfunction "2_2") (pintype "passive"))
    )
    (net (code "55") (name "/FPGA0_RX1_R_P") (class "Default")
      (node (ref "J23") (pin "1") (pinfunction "1_1") (pintype "passive"))
      (node (ref "R244") (pin "2") (pinfunction "2_2") (pintype "passive"))
      (node (ref "R248") (pin "2") (pinfunction "2_2") (pintype "passive"))
    )
    (net (code "56") (name "/FPGA0_RX2_N") (class "Default")
      (node (ref "R256") (pin "1") (pinfunction "1_1") (pintype "passive"))
      (node (ref "R261") (pin "1") (pinfunction "1_1") (pintype "passive"))
    )
    (net (code "57") (name "/FPGA0_RX2_P") (class "Default")
      (node (ref "R254") (pin "1") (pinfunction "1_1") (pintype "passive"))
      (node (ref "R256") (pin "2") (pinfunction "2_2") (pintype "passive"))
    )
    (net (code "58") (name "/FPGA0_RX2_R_N") (class "Default")
      (node (ref "J24") (pin "2") (pinfunction "2_2") (pintype "passive"))
      (node (ref "J24") (pin "3") (pinfunction "3_3") (pintype "passive"))
      (node (ref "J24") (pin "4") (pinfunction "4_4") (pintype "passive"))
      (node (ref "J24") (pin "5") (pinfunction "5_5") (pintype "passive"))
      (node (ref "R257") (pin "1") (pinfunction "1_1") (pintype "passive"))
      (node (ref "R261") (pin "2") (pinfunction "2_2") (pintype "passive"))
    )
    (net (code "59") (name "/FPGA0_RX2_R_P") (class "Default")
      (node (ref "J24") (pin "1") (pinfunction "1_1") (pintype "passive"))
      (node (ref "R254") (pin "2") (pinfunction "2_2") (pintype "passive"))
      (node (ref "R257") (pin "2") (pinfunction "2_2") (pintype "passive"))
    )
    (net (code "60") (name "/FPGA0_RX3_N") (class "Default")
      (node (ref "R258") (pin "1") (pinfunction "1_1") (pintype "passive"))
      (node (ref "R262") (pin "1") (pinfunction "1_1") (pintype "passive"))
    )
    (net (code "61") (name "/FPGA0_RX3_P") (class "Default")
      (node (ref "R255") (pin "1") (pinfunction "1_1") (pintype "passive"))
      (node (ref "R258") (pin "2") (pinfunction "2_2") (pintype "passive"))
    )
    (net (code "62") (name "/FPGA0_RX3_R_N") (class "Default")
      (node (ref "J25") (pin "2") (pinfunction "2_2") (pintype "passive"))
      (node (ref "J25") (pin "3") (pinfunction "3_3") (pintype "passive"))
      (node (ref "J25") (pin "4") (pinfunction "4_4") (pintype "passive"))
      (node (ref "J25") (pin "5") (pinfunction "5_5") (pintype "passive"))
      (node (ref "R259") (pin "1") (pinfunction "1_1") (pintype "passive"))
      (node (ref "R262") (pin "2") (pinfunction "2_2") (pintype "passive"))
    )
    (net (code "63") (name "/FPGA0_RX3_R_P") (class "Default")
      (node (ref "J25") (pin "1") (pinfunction "1_1") (pintype "passive"))
      (node (ref "R255") (pin "2") (pinfunction "2_2") (pintype "passive"))
      (node (ref "R259") (pin "2") (pinfunction "2_2") (pintype "passive"))
    )
    (net (code "64") (name "/FPGA0_TX0_N") (class "Default")
      (node (ref "R227") (pin "1") (pinfunction "1_1") (pintype "passive"))
      (node (ref "R231") (pin "1") (pinfunction "1_1") (pintype "passive"))
    )
    (net (code "65") (name "/FPGA0_TX0_P") (class "Default")
      (node (ref "R225") (pin "1") (pinfunction "1_1") (pintype "passive"))
      (node (ref "R227") (pin "2") (pinfunction "2_2") (pintype "passive"))
    )
    (net (code "66") (name "/FPGA0_TX0_R_N") (class "Default")
      (node (ref "J18") (pin "2") (pinfunction "2_2") (pintype "passive"))
      (node (ref "J18") (pin "3") (pinfunction "3_3") (pintype "passive"))
      (node (ref "J18") (pin "4") (pinfunction "4_4") (pintype "passive"))
      (node (ref "J18") (pin "5") (pinfunction "5_5") (pintype "passive"))
      (node (ref "R228") (pin "1") (pinfunction "1_1") (pintype "passive"))
      (node (ref "R231") (pin "2") (pinfunction "2_2") (pintype "passive"))
    )
    (net (code "67") (name "/FPGA0_TX0_R_P") (class "Default")
      (node (ref "J18") (pin "1") (pinfunction "1_1") (pintype "passive"))
      (node (ref "R225") (pin "2") (pinfunction "2_2") (pintype "passive"))
      (node (ref "R228") (pin "2") (pinfunction "2_2") (pintype "passive"))
    )
    (net (code "68") (name "/FPGA0_TX1_N") (class "Default")
      (node (ref "R229") (pin "1") (pinfunction "1_1") (pintype "passive"))
      (node (ref "R232") (pin "1") (pinfunction "1_1") (pintype "passive"))
    )
    (net (code "69") (name "/FPGA0_TX1_P") (class "Default")
      (node (ref "R226") (pin "1") (pinfunction "1_1") (pintype "passive"))
      (node (ref "R229") (pin "2") (pinfunction "2_2") (pintype "passive"))
    )
    (net (code "70") (name "/FPGA0_TX1_R_N") (class "Default")
      (node (ref "J19") (pin "2") (pinfunction "2_2") (pintype "passive"))
      (node (ref "J19") (pin "3") (pinfunction "3_3") (pintype "passive"))
      (node (ref "J19") (pin "4") (pinfunction "4_4") (pintype "passive"))
      (node (ref "J19") (pin "5") (pinfunction "5_5") (pintype "passive"))
      (node (ref "R230") (pin "1") (pinfunction "1_1") (pintype "passive"))
      (node (ref "R232") (pin "2") (pinfunction "2_2") (pintype "passive"))
    )
    (net (code "71") (name "/FPGA0_TX1_R_P") (class "Default")
      (node (ref "J19") (pin "1") (pinfunction "1_1") (pintype "passive"))
      (node (ref "R226") (pin "2") (pinfunction "2_2") (pintype "passive"))
      (node (ref "R230") (pin "2") (pinfunction "2_2") (pintype "passive"))
    )
    (net (code "72") (name "/FPGA0_TX2_N") (class "Default")
      (node (ref "R235") (pin "1") (pinfunction "1_1") (pintype "passive"))
      (node (ref "R239") (pin "1") (pinfunction "1_1") (pintype "passive"))
    )
    (net (code "73") (name "/FPGA0_TX2_P") (class "Default")
      (node (ref "R233") (pin "1") (pinfunction "1_1") (pintype "passive"))
      (node (ref "R235") (pin "2") (pinfunction "2_2") (pintype "passive"))
    )
    (net (code "74") (name "/FPGA0_TX2_R_N") (class "Default")
      (node (ref "J20") (pin "2") (pinfunction "2_2") (pintype "passive"))
      (node (ref "J20") (pin "3") (pinfunction "3_3") (pintype "passive"))
      (node (ref "J20") (pin "4") (pinfunction "4_4") (pintype "passive"))
      (node (ref "J20") (pin "5") (pinfunction "5_5") (pintype "passive"))
      (node (ref "R236") (pin "1") (pinfunction "1_1") (pintype "passive"))
      (node (ref "R239") (pin "2") (pinfunction "2_2") (pintype "passive"))
    )
    (net (code "75") (name "/FPGA0_TX2_R_P") (class "Default")
      (node (ref "J20") (pin "1") (pinfunction "1_1") (pintype "passive"))
      (node (ref "R233") (pin "2") (pinfunction "2_2") (pintype "passive"))
      (node (ref "R236") (pin "2") (pinfunction "2_2") (pintype "passive"))
    )
    (net (code "76") (name "/FPGA0_TX3_N") (class "Default")
      (node (ref "R237") (pin "1") (pinfunction "1_1") (pintype "passive"))
      (node (ref "R240") (pin "1") (pinfunction "1_1") (pintype "passive"))
    )
    (net (code "77") (name "/FPGA0_TX3_P") (class "Default")
      (node (ref "R234") (pin "1") (pinfunction "1_1") (pintype "passive"))
      (node (ref "R237") (pin "2") (pinfunction "2_2") (pintype "passive"))
    )
    (net (code "78") (name "/FPGA0_TX3_R_N") (class "Default")
      (node (ref "J21") (pin "2") (pinfunction "2_2") (pintype "passive"))
      (node (ref "J21") (pin "3") (pinfunction "3_3") (pintype "passive"))
      (node (ref "J21") (pin "4") (pinfunction "4_4") (pintype "passive"))
      (node (ref "J21") (pin "5") (pinfunction "5_5") (pintype "passive"))
      (node (ref "R238") (pin "1") (pinfunction "1_1") (pintype "passive"))
      (node (ref "R240") (pin "2") (pinfunction "2_2") (pintype "passive"))
    )
    (net (code "79") (name "/FPGA0_TX3_R_P") (class "Default")
      (node (ref "J21") (pin "1") (pinfunction "1_1") (pintype "passive"))
      (node (ref "R234") (pin "2") (pinfunction "2_2") (pintype "passive"))
      (node (ref "R238") (pin "2") (pinfunction "2_2") (pintype "passive"))
    )
    (net (code "80") (name "GND") (class "Default")
      (node (ref "C298") (pin "2") (pinfunction "2_2") (pintype "passive"))
      (node (ref "C299") (pin "2") (pinfunction "2_2") (pintype "passive"))
      (node (ref "C301") (pin "2") (pinfunction "2_2") (pintype "passive"))
      (node (ref "C302") (pin "2") (pinfunction "2_2") (pintype "passive"))
      (node (ref "C304") (pin "2") (pinfunction "2_2") (pintype "passive"))
      (node (ref "C305") (pin "2") (pinfunction "2_2") (pintype "passive"))
      (node (ref "C306") (pin "2") (pinfunction "2_2") (pintype "passive"))
      (node (ref "C307") (pin "2") (pinfunction "2_2") (pintype "passive"))
      (node (ref "J17") (pin "11") (pinfunction "GND4_11") (pintype "power_in"))
      (node (ref "J17") (pin "16") (pinfunction "GND6_16") (pintype "power_in"))
      (node (ref "J17") (pin "19") (pinfunction "RTN_19") (pintype "passive"))
      (node (ref "J17") (pin "2") (pinfunction "GND1_2") (pintype "power_in"))
      (node (ref "J17") (pin "5") (pinfunction "GND2_5") (pintype "power_in"))
      (node (ref "J17") (pin "8") (pinfunction "GND3_8") (pintype "power_in"))
      (node (ref "J27") (pin "11") (pinfunction "GND4_11") (pintype "power_in"))
      (node (ref "J27") (pin "16") (pinfunction "GND6_16") (pintype "power_in"))
      (node (ref "J27") (pin "19") (pinfunction "RTN_19") (pintype "passive"))
      (node (ref "J27") (pin "2") (pinfunction "GND1_2") (pintype "power_in"))
      (node (ref "J27") (pin "5") (pinfunction "GND2_5") (pintype "power_in"))
      (node (ref "J27") (pin "8") (pinfunction "GND3_8") (pintype "power_in"))
      (node (ref "R242") (pin "2") (pinfunction "2_2") (pintype "passive"))
      (node (ref "R251") (pin "1") (pinfunction "1_1") (pintype "passive"))
      (node (ref "R252") (pin "1") (pinfunction "1_1") (pintype "passive"))
      (node (ref "R253") (pin "1") (pinfunction "1_1") (pintype "passive"))
      (node (ref "R268") (pin "2") (pinfunction "2_2") (pintype "passive"))
      (node (ref "R269") (pin "1") (pinfunction "1_1") (pintype "passive"))
      (node (ref "R270") (pin "1") (pinfunction "1_1") (pintype "passive"))
      (node (ref "R271") (pin "1") (pinfunction "1_1") (pintype "passive"))
      (node (ref "R279") (pin "2") (pinfunction "2_2") (pintype "passive"))
      (node (ref "R280") (pin "1") (pinfunction "1_1") (pintype "passive"))
      (node (ref "U30") (pin "11") (pinfunction "GND_11") (pintype "power_in"))
      (node (ref "U30") (pin "2") (pinfunction "GND_2") (pintype "power_in"))
      (node (ref "U30") (pin "5") (pinfunction "GND_5") (pintype "power_in"))
      (node (ref "U30") (pin "8") (pinfunction "GND_8") (pintype "power_in"))
      (node (ref "U31") (pin "3") (pinfunction "GND_3") (pintype "power_in"))
      (node (ref "U32") (pin "11") (pinfunction "GND_11") (pintype "power_in"))
      (node (ref "U32") (pin "2") (pinfunction "GND_2") (pintype "power_in"))
      (node (ref "U32") (pin "5") (pinfunction "GND_5") (pintype "power_in"))
      (node (ref "U32") (pin "8") (pinfunction "GND_8") (pintype "power_in"))
      (node (ref "U33") (pin "3") (pinfunction "GND_3") (pintype "power_in"))
    )
    (net (code "81") (name "Net-(J17-GND10)") (class "Default")
      (node (ref "J17") (pin "21") (pinfunction "GND7_21") (pintype "power_in"))
      (node (ref "J17") (pin "22") (pinfunction "GND8_22") (pintype "power_in"))
      (node (ref "J17") (pin "23") (pinfunction "GND9_23") (pintype "power_in"))
      (node (ref "J17") (pin "24") (pinfunction "GND10_24") (pintype "power_in"))
      (node (ref "R279") (pin "1") (pinfunction "1_1") (pintype "passive"))
    )
    (net (code "82") (name "Net-(J27-GND10)") (class "Default")
      (node (ref "J27") (pin "21") (pinfunction "GND7_21") (pintype "power_in"))
      (node (ref "J27") (pin "22") (pinfunction "GND8_22") (pintype "power_in"))
      (node (ref "J27") (pin "23") (pinfunction "GND9_23") (pintype "power_in"))
      (node (ref "J27") (pin "24") (pinfunction "GND10_24") (pintype "power_in"))
      (node (ref "R280") (pin "2") (pinfunction "2_2") (pintype "passive"))
    )
    (net (code "83") (name "unconnected-(U30-NC-Pad14)") (class "Default")
      (node (ref "U30") (pin "14") (pinfunction "NC_14") (pintype "passive+no_connect"))
    )
    (net (code "84") (name "unconnected-(U31-IO4-Pad5)") (class "Default")
      (node (ref "U31") (pin "5") (pinfunction "IO4_5") (pintype "passive+no_connect"))
    )
    (net (code "85") (name "unconnected-(U32-NC-Pad14)") (class "Default")
      (node (ref "U32") (pin "14") (pinfunction "NC_14") (pintype "passive+no_connect"))
    )
    (net (code "86") (name "unconnected-(U33-IO4-Pad5)") (class "Default")
      (node (ref "U33") (pin "5") (pinfunction "IO4_5") (pintype "passive+no_connect"))
    )
  )
)
